# BLE_--_HM-10_ATtiny85_Combo_--_v04.net
KiCad netlist of a schematic drawn in EAGLE
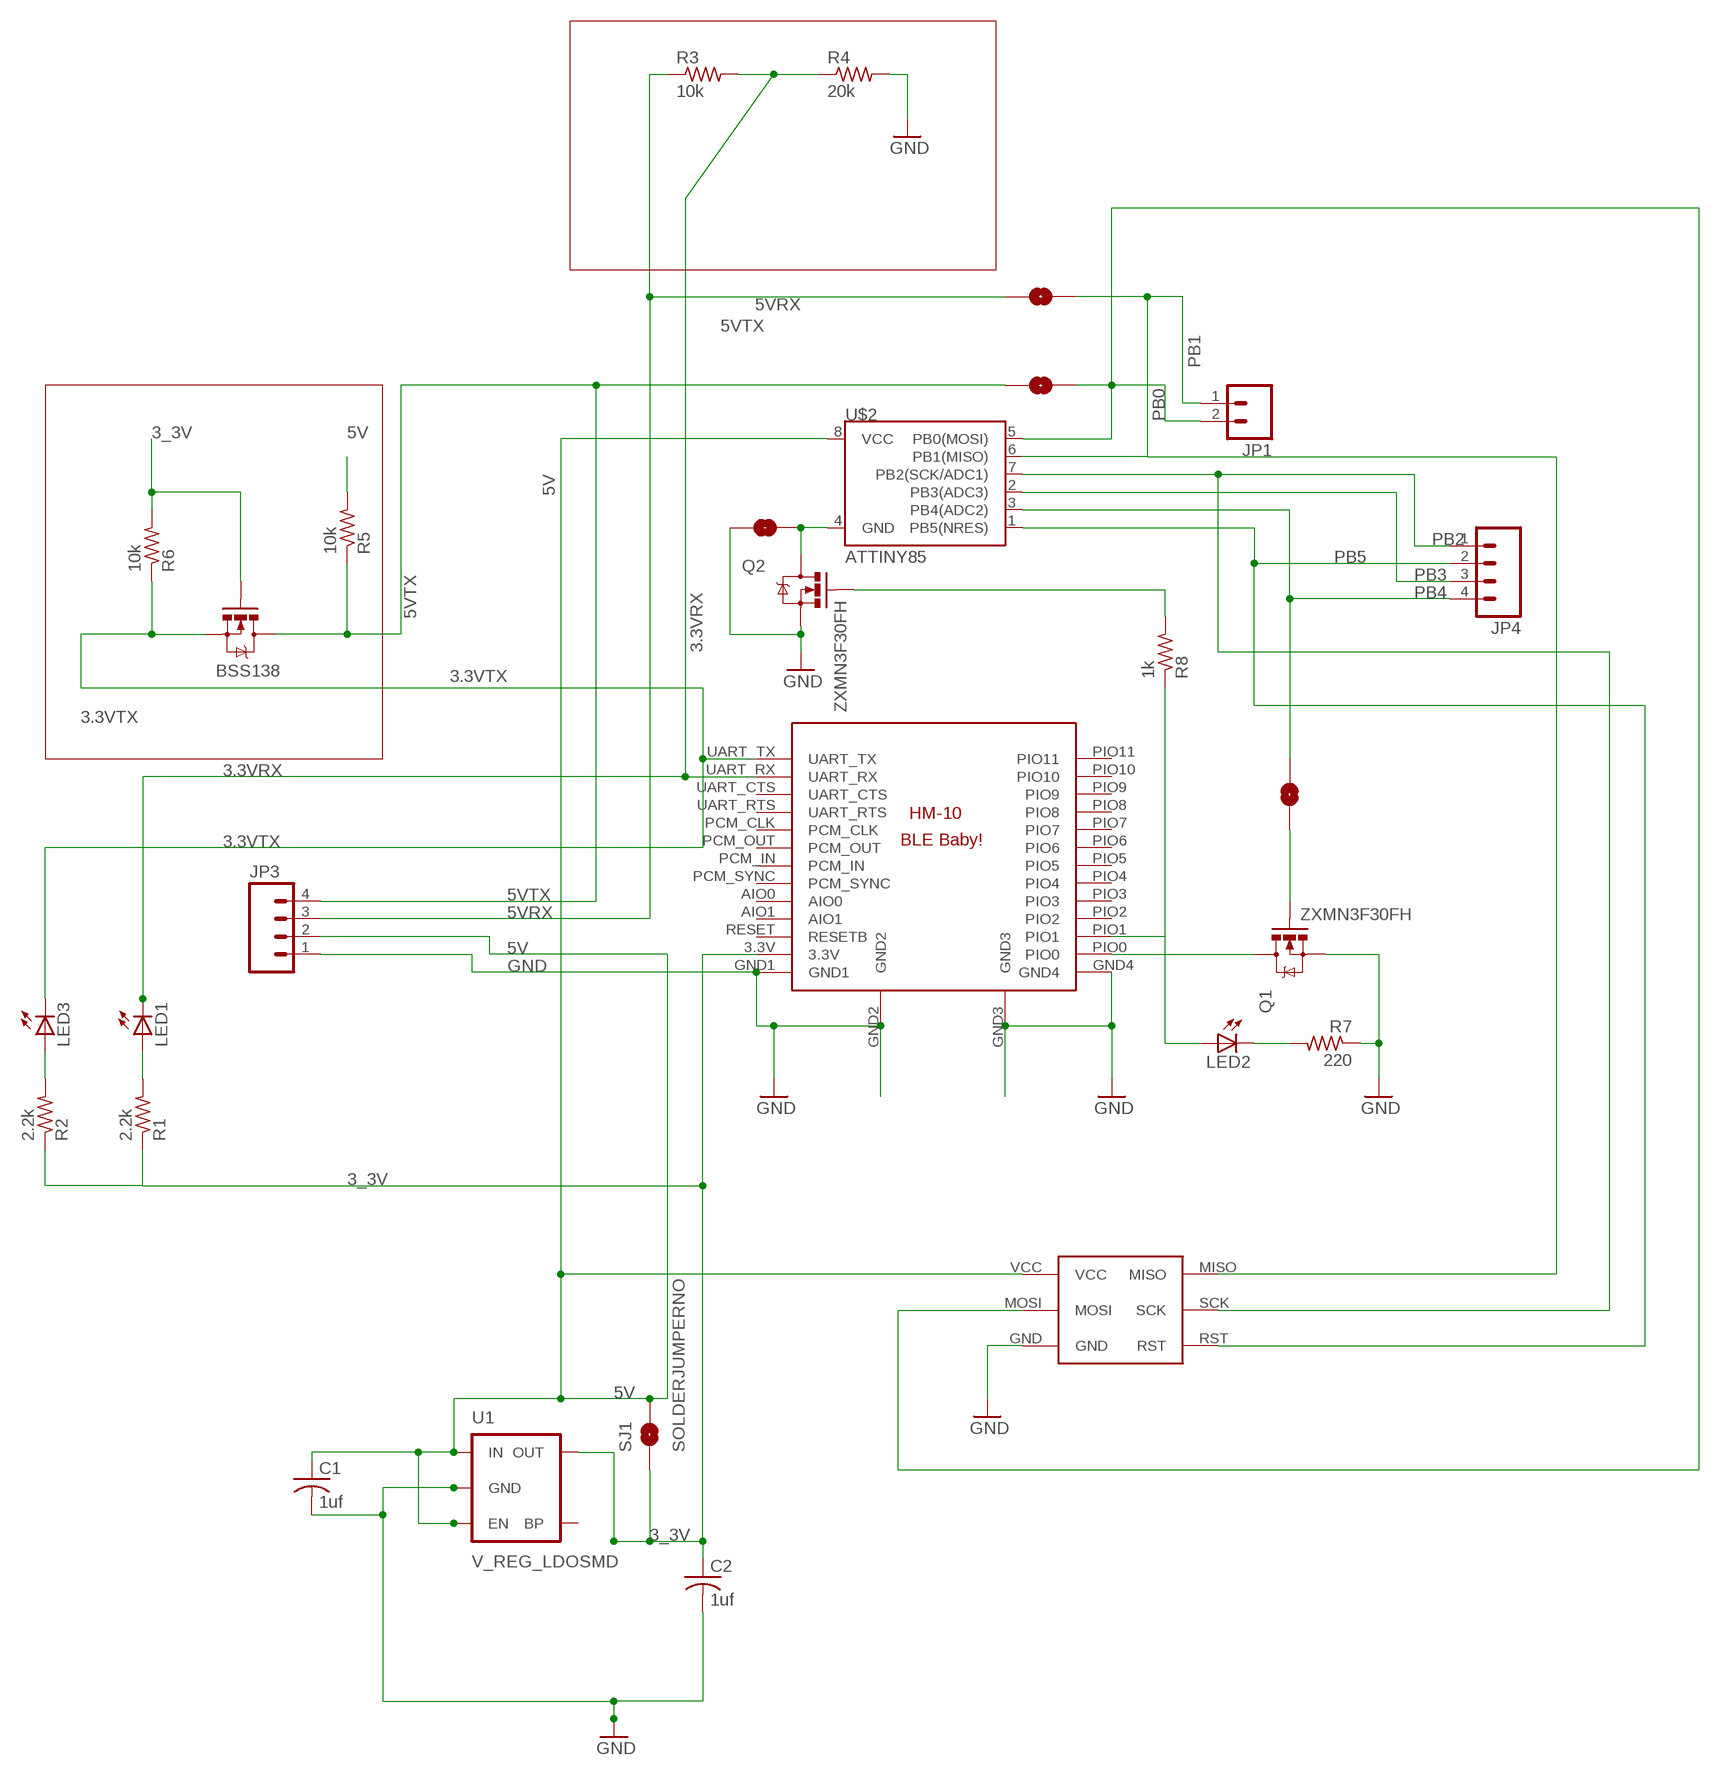
[diagram p0: schematic, sheet 1]

(export (version "E")
  (design (tool "Eeschema 10.0.6"))
  (components
    (comp (ref "BSS138")
      (value "MOSFET-NCHANNELSMD")
      (footprint "eagle-import:SOT23-3")
      (libsource (lib "eagle-import") (part "MOSFET-NCHANNELSMD"))
    )
    (comp (ref "C1")
      (value "1uf")
      (footprint "eagle-import:C0402")
      (libsource (lib "eagle-import") (part "C-USC0402"))
    )
    (comp (ref "C2")
      (value "1uf")
      (footprint "eagle-import:C0402")
      (libsource (lib "eagle-import") (part "C-USC0402"))
    )
    (comp (ref "JP1")
      (value "M02PTH")
      (footprint "eagle-import:1X02")
      (libsource (lib "eagle-import") (part "M02PTH"))
    )
    (comp (ref "JP3")
      (value "M04PTH")
      (footprint "eagle-import:1X04")
      (libsource (lib "eagle-import") (part "M04PTH"))
    )
    (comp (ref "JP4")
      (value "M04PTH")
      (footprint "eagle-import:1X04")
      (libsource (lib "eagle-import") (part "M04PTH"))
    )
    (comp (ref "LED1")
      (value "LED0603")
      (footprint "eagle-import:LED-0603")
      (libsource (lib "eagle-import") (part "LED0603"))
    )
    (comp (ref "LED2")
      (value "LED0603")
      (footprint "eagle-import:LED-0603")
      (libsource (lib "eagle-import") (part "LED0603"))
    )
    (comp (ref "LED3")
      (value "LED0603")
      (footprint "eagle-import:LED-0603")
      (libsource (lib "eagle-import") (part "LED0603"))
    )
    (comp (ref "Q1")
      (value "ZXMN3F30FH")
      (footprint "eagle-import:SOT23-3")
      (libsource (lib "eagle-import") (part "MOSFET-NCHANNELSMD"))
    )
    (comp (ref "Q2")
      (value "ZXMN3F30FH")
      (footprint "eagle-import:SOT23-3")
      (libsource (lib "eagle-import") (part "MOSFET-NCHANNELSMD"))
    )
    (comp (ref "R1")
      (value "2.2k")
      (footprint "eagle-import:R0402")
      (libsource (lib "eagle-import") (part "R-US_R0402"))
    )
    (comp (ref "R2")
      (value "2.2k")
      (footprint "eagle-import:R0402")
      (libsource (lib "eagle-import") (part "R-US_R0402"))
    )
    (comp (ref "R3")
      (value "10k")
      (footprint "eagle-import:R0402")
      (libsource (lib "eagle-import") (part "R-US_R0402"))
    )
    (comp (ref "R4")
      (value "20k")
      (footprint "eagle-import:R0402")
      (libsource (lib "eagle-import") (part "R-US_R0402"))
    )
    (comp (ref "R5")
      (value "10k")
      (footprint "eagle-import:R0402")
      (libsource (lib "eagle-import") (part "R-US_R0402"))
    )
    (comp (ref "R6")
      (value "10k")
      (footprint "eagle-import:R0402")
      (libsource (lib "eagle-import") (part "R-US_R0402"))
    )
    (comp (ref "R7")
      (value "220")
      (footprint "eagle-import:R0402")
      (libsource (lib "eagle-import") (part "R-US_R0402"))
    )
    (comp (ref "R8")
      (value "1k")
      (footprint "eagle-import:R0402")
      (libsource (lib "eagle-import") (part "R-US_R0402"))
    )
    (comp (ref "SJ1")
      (value "SOLDERJUMPERNO")
      (footprint "eagle-import:SJ_2S-NO")
      (libsource (lib "eagle-import") (part "SOLDERJUMPERNO"))
    )
    (comp (ref "SJ2")
      (value "SOLDERJUMPERNO")
      (footprint "eagle-import:SJ_2S-NO")
      (libsource (lib "eagle-import") (part "SOLDERJUMPERNO"))
    )
    (comp (ref "SJ3")
      (value "SOLDERJUMPERNO")
      (footprint "eagle-import:SJ_2S-NO")
      (libsource (lib "eagle-import") (part "SOLDERJUMPERNO"))
    )
    (comp (ref "SJ4")
      (value "SOLDERJUMPERNO")
      (footprint "eagle-import:SJ_2S-NO")
      (libsource (lib "eagle-import") (part "SOLDERJUMPERNO"))
    )
    (comp (ref "SJ5")
      (value "SOLDERJUMPERNO")
      (footprint "eagle-import:SJ_2S-NO")
      (libsource (lib "eagle-import") (part "SOLDERJUMPERNO"))
    )
    (comp (ref "U$1")
      (value "BLE-HM10_NO_SPI")
      (footprint "eagle-import:BLE-HM10_NO_SPI")
      (libsource (lib "eagle-import") (part "BLE-HM10_NO_SPI"))
    )
    (comp (ref "U$2")
      (value "ATTINY85")
      (footprint "eagle-import:SO08-EIAJ")
      (libsource (lib "eagle-import") (part "ATTINY45"))
    )
    (comp (ref "U$4")
      (value "POGO_PIN_SPI_PAD")
      (footprint "eagle-import:POGO_PIN_SPI_PAD")
      (libsource (lib "eagle-import") (part "POGO_PIN_SPI_PAD"))
    )
    (comp (ref "U1")
      (value "V_REG_LDOSMD")
      (footprint "eagle-import:SOT23-5")
      (libsource (lib "eagle-import") (part "V_REG_LDOSMD"))
    )
  )
  (nets
    (net (code "1") (name "/3.3VRX") (class "Default")
      (node (ref "LED1") (pin "C") (pinfunction "C_C") (pintype "passive"))
      (node (ref "R3") (pin "2") (pinfunction "2_2") (pintype "passive"))
      (node (ref "R4") (pin "1") (pinfunction "1_1") (pintype "passive"))
      (node (ref "U$1") (pin "UART_RX") (pinfunction "UART_RX_UART_RX") (pintype "bidirectional"))
    )
    (net (code "2") (name "/3.3VTX") (class "Default")
      (node (ref "BSS138") (pin "2") (pinfunction "S_2") (pintype "passive"))
      (node (ref "LED3") (pin "C") (pinfunction "C_C") (pintype "passive"))
      (node (ref "R6") (pin "1") (pinfunction "1_1") (pintype "passive"))
      (node (ref "U$1") (pin "UART_TX") (pinfunction "UART_TX_UART_TX") (pintype "bidirectional"))
    )
    (net (code "3") (name "/3_3V") (class "Default")
      (node (ref "BSS138") (pin "1") (pinfunction "G_1") (pintype "passive"))
      (node (ref "C2") (pin "1") (pinfunction "1_1") (pintype "passive"))
      (node (ref "R1") (pin "1") (pinfunction "1_1") (pintype "passive"))
      (node (ref "R2") (pin "1") (pinfunction "1_1") (pintype "passive"))
      (node (ref "R6") (pin "2") (pinfunction "2_2") (pintype "passive"))
      (node (ref "SJ1") (pin "1") (pinfunction "1_1") (pintype "passive"))
      (node (ref "U$1") (pin "3.3V") (pinfunction "3.3V_3.3V") (pintype "bidirectional"))
      (node (ref "U1") (pin "5") (pinfunction "OUT_5") (pintype "passive"))
    )
    (net (code "4") (name "/5V") (class "Default")
      (node (ref "C1") (pin "1") (pinfunction "1_1") (pintype "passive"))
      (node (ref "JP3") (pin "2") (pinfunction "2_2") (pintype "passive"))
      (node (ref "R5") (pin "2") (pinfunction "2_2") (pintype "passive"))
      (node (ref "SJ1") (pin "2") (pinfunction "2_2") (pintype "passive"))
      (node (ref "U$2") (pin "8") (pinfunction "VCC_8") (pintype "bidirectional"))
      (node (ref "U$4") (pin "VCC") (pinfunction "VCC_VCC") (pintype "bidirectional"))
      (node (ref "U1") (pin "1") (pinfunction "IN_1") (pintype "input"))
      (node (ref "U1") (pin "3") (pinfunction "EN_3") (pintype "input"))
    )
    (net (code "5") (name "/5VRX") (class "Default")
      (node (ref "JP3") (pin "3") (pinfunction "3_3") (pintype "passive"))
      (node (ref "R3") (pin "1") (pinfunction "1_1") (pintype "passive"))
      (node (ref "SJ3") (pin "2") (pinfunction "2_2") (pintype "passive"))
    )
    (net (code "6") (name "/5VTX") (class "Default")
      (node (ref "BSS138") (pin "3") (pinfunction "D_3") (pintype "passive"))
      (node (ref "JP3") (pin "4") (pinfunction "4_4") (pintype "passive"))
      (node (ref "R5") (pin "1") (pinfunction "1_1") (pintype "passive"))
      (node (ref "SJ2") (pin "2") (pinfunction "2_2") (pintype "passive"))
    )
    (net (code "7") (name "/PB0") (class "Default")
      (node (ref "JP1") (pin "2") (pinfunction "2_2") (pintype "passive"))
      (node (ref "SJ2") (pin "1") (pinfunction "1_1") (pintype "passive"))
      (node (ref "U$2") (pin "5") (pinfunction "PB0(MOSI)_5") (pintype "bidirectional"))
      (node (ref "U$4") (pin "MOSI") (pinfunction "MOSI_MOSI") (pintype "bidirectional"))
    )
    (net (code "8") (name "/PB1") (class "Default")
      (node (ref "JP1") (pin "1") (pinfunction "1_1") (pintype "passive"))
      (node (ref "SJ3") (pin "1") (pinfunction "1_1") (pintype "passive"))
      (node (ref "U$2") (pin "6") (pinfunction "PB1(MISO)_6") (pintype "bidirectional"))
      (node (ref "U$4") (pin "MISO") (pinfunction "MISO_MISO") (pintype "bidirectional"))
    )
    (net (code "9") (name "/PB2") (class "Default")
      (node (ref "JP4") (pin "1") (pinfunction "1_1") (pintype "passive"))
      (node (ref "U$2") (pin "7") (pinfunction "PB2(SCK/ADC1)_7") (pintype "bidirectional"))
      (node (ref "U$4") (pin "SCK") (pinfunction "SCK_SCK") (pintype "bidirectional"))
    )
    (net (code "10") (name "/PB3") (class "Default")
      (node (ref "JP4") (pin "3") (pinfunction "3_3") (pintype "passive"))
      (node (ref "U$2") (pin "2") (pinfunction "PB3(ADC3)_2") (pintype "bidirectional"))
    )
    (net (code "11") (name "/PB4") (class "Default")
      (node (ref "JP4") (pin "4") (pinfunction "4_4") (pintype "passive"))
      (node (ref "SJ4") (pin "1") (pinfunction "1_1") (pintype "passive"))
      (node (ref "U$2") (pin "3") (pinfunction "PB4(ADC2)_3") (pintype "bidirectional"))
    )
    (net (code "12") (name "/PB5") (class "Default")
      (node (ref "JP4") (pin "2") (pinfunction "2_2") (pintype "passive"))
      (node (ref "U$2") (pin "1") (pinfunction "PB5(NRES)_1") (pintype "bidirectional"))
      (node (ref "U$4") (pin "RST") (pinfunction "RST_RST") (pintype "bidirectional"))
    )
    (net (code "13") (name "GND") (class "Default")
      (node (ref "C1") (pin "2") (pinfunction "2_2") (pintype "passive"))
      (node (ref "C2") (pin "2") (pinfunction "2_2") (pintype "passive"))
      (node (ref "JP3") (pin "1") (pinfunction "1_1") (pintype "passive"))
      (node (ref "Q1") (pin "2") (pinfunction "S_2") (pintype "passive"))
      (node (ref "Q2") (pin "2") (pinfunction "S_2") (pintype "passive"))
      (node (ref "R4") (pin "2") (pinfunction "2_2") (pintype "passive"))
      (node (ref "R7") (pin "1") (pinfunction "1_1") (pintype "passive"))
      (node (ref "SJ5") (pin "1") (pinfunction "1_1") (pintype "passive"))
      (node (ref "U$1") (pin "GND1") (pinfunction "GND1_GND1") (pintype "bidirectional"))
      (node (ref "U$1") (pin "GND2") (pinfunction "GND2_GND2") (pintype "bidirectional"))
      (node (ref "U$1") (pin "GND3") (pinfunction "GND3_GND3") (pintype "bidirectional"))
      (node (ref "U$1") (pin "GND4") (pinfunction "GND4_GND4") (pintype "bidirectional"))
      (node (ref "U$4") (pin "GND") (pinfunction "GND_GND") (pintype "bidirectional"))
      (node (ref "U1") (pin "2") (pinfunction "GND_2") (pintype "input"))
    )
    (net (code "14") (name "Net-(LED1-PadA)") (class "Default")
      (node (ref "LED1") (pin "A") (pinfunction "A_A") (pintype "passive"))
      (node (ref "R1") (pin "2") (pinfunction "2_2") (pintype "passive"))
    )
    (net (code "15") (name "Net-(LED2-PadA)") (class "Default")
      (node (ref "LED2") (pin "A") (pinfunction "A_A") (pintype "passive"))
      (node (ref "R8") (pin "1") (pinfunction "1_1") (pintype "passive"))
      (node (ref "U$1") (pin "PIO1") (pinfunction "PIO1_PIO1") (pintype "bidirectional"))
    )
    (net (code "16") (name "Net-(LED2-PadC)") (class "Default")
      (node (ref "LED2") (pin "C") (pinfunction "C_C") (pintype "passive"))
      (node (ref "R7") (pin "2") (pinfunction "2_2") (pintype "passive"))
    )
    (net (code "17") (name "Net-(LED3-PadA)") (class "Default")
      (node (ref "LED3") (pin "A") (pinfunction "A_A") (pintype "passive"))
      (node (ref "R2") (pin "2") (pinfunction "2_2") (pintype "passive"))
    )
    (net (code "18") (name "Net-(Q1-D)") (class "Default")
      (node (ref "Q1") (pin "3") (pinfunction "D_3") (pintype "passive"))
      (node (ref "U$1") (pin "PIO0") (pinfunction "PIO0_PIO0") (pintype "bidirectional"))
    )
    (net (code "19") (name "Net-(Q1-G)") (class "Default")
      (node (ref "Q1") (pin "1") (pinfunction "G_1") (pintype "passive"))
      (node (ref "SJ4") (pin "2") (pinfunction "2_2") (pintype "passive"))
    )
    (net (code "20") (name "Net-(Q2-D)") (class "Default")
      (node (ref "Q2") (pin "3") (pinfunction "D_3") (pintype "passive"))
      (node (ref "SJ5") (pin "2") (pinfunction "2_2") (pintype "passive"))
      (node (ref "U$2") (pin "4") (pinfunction "GND_4") (pintype "bidirectional"))
    )
    (net (code "21") (name "Net-(Q2-G)") (class "Default")
      (node (ref "Q2") (pin "1") (pinfunction "G_1") (pintype "passive"))
      (node (ref "R8") (pin "2") (pinfunction "2_2") (pintype "passive"))
    )
    (net (code "22") (name "unconnected-(U$1-PadAIO0)") (class "Default")
      (node (ref "U$1") (pin "AIO0") (pinfunction "AIO0_AIO0") (pintype "bidirectional"))
    )
    (net (code "23") (name "unconnected-(U$1-PadAIO1)") (class "Default")
      (node (ref "U$1") (pin "AIO1") (pinfunction "AIO1_AIO1") (pintype "bidirectional"))
    )
    (net (code "24") (name "unconnected-(U$1-PadPCM_CLK)") (class "Default")
      (node (ref "U$1") (pin "PCM_CLK") (pinfunction "PCM_CLK_PCM_CLK") (pintype "bidirectional"))
    )
    (net (code "25") (name "unconnected-(U$1-PadPCM_IN)") (class "Default")
      (node (ref "U$1") (pin "PCM_IN") (pinfunction "PCM_IN_PCM_IN") (pintype "bidirectional"))
    )
    (net (code "26") (name "unconnected-(U$1-PadPCM_OUT)") (class "Default")
      (node (ref "U$1") (pin "PCM_OUT") (pinfunction "PCM_OUT_PCM_OUT") (pintype "bidirectional"))
    )
    (net (code "27") (name "unconnected-(U$1-PadPCM_SYNC)") (class "Default")
      (node (ref "U$1") (pin "PCM_SYNC") (pinfunction "PCM_SYNC_PCM_SYNC") (pintype "bidirectional"))
    )
    (net (code "28") (name "unconnected-(U$1-PadPIO2)") (class "Default")
      (node (ref "U$1") (pin "PIO2") (pinfunction "PIO2_PIO2") (pintype "bidirectional"))
    )
    (net (code "29") (name "unconnected-(U$1-PadPIO3)") (class "Default")
      (node (ref "U$1") (pin "PIO3") (pinfunction "PIO3_PIO3") (pintype "bidirectional"))
    )
    (net (code "30") (name "unconnected-(U$1-PadPIO4)") (class "Default")
      (node (ref "U$1") (pin "PIO4") (pinfunction "PIO4_PIO4") (pintype "bidirectional"))
    )
    (net (code "31") (name "unconnected-(U$1-PadPIO5)") (class "Default")
      (node (ref "U$1") (pin "PIO5") (pinfunction "PIO5_PIO5") (pintype "bidirectional"))
    )
    (net (code "32") (name "unconnected-(U$1-PadPIO6)") (class "Default")
      (node (ref "U$1") (pin "PIO6") (pinfunction "PIO6_PIO6") (pintype "bidirectional"))
    )
    (net (code "33") (name "unconnected-(U$1-PadPIO7)") (class "Default")
      (node (ref "U$1") (pin "PIO7") (pinfunction "PIO7_PIO7") (pintype "bidirectional"))
    )
    (net (code "34") (name "unconnected-(U$1-PadPIO8)") (class "Default")
      (node (ref "U$1") (pin "PIO8") (pinfunction "PIO8_PIO8") (pintype "bidirectional"))
    )
    (net (code "35") (name "unconnected-(U$1-PadPIO9)") (class "Default")
      (node (ref "U$1") (pin "PIO9") (pinfunction "PIO9_PIO9") (pintype "bidirectional"))
    )
    (net (code "36") (name "unconnected-(U$1-PadPIO10)") (class "Default")
      (node (ref "U$1") (pin "PIO10") (pinfunction "PIO10_PIO10") (pintype "bidirectional"))
    )
    (net (code "37") (name "unconnected-(U$1-PadPIO11)") (class "Default")
      (node (ref "U$1") (pin "PIO11") (pinfunction "PIO11_PIO11") (pintype "bidirectional"))
    )
    (net (code "38") (name "unconnected-(U$1-PadUART_CTS)") (class "Default")
      (node (ref "U$1") (pin "UART_CTS") (pinfunction "UART_CTS_UART_CTS") (pintype "bidirectional"))
    )
    (net (code "39") (name "unconnected-(U$1-PadUART_RTS)") (class "Default")
      (node (ref "U$1") (pin "UART_RTS") (pinfunction "UART_RTS_UART_RTS") (pintype "bidirectional"))
    )
    (net (code "40") (name "unconnected-(U$1-RESETB-PadRESET)") (class "Default")
      (node (ref "U$1") (pin "RESET") (pinfunction "RESETB_RESET") (pintype "bidirectional"))
    )
    (net (code "41") (name "unconnected-(U1-BP-Pad4)") (class "Default")
      (node (ref "U1") (pin "4") (pinfunction "BP_4") (pintype "input"))
    )
  )
)
